# LedLampDriver.net
KiCad netlist of a schematic drawn in Altium Designer
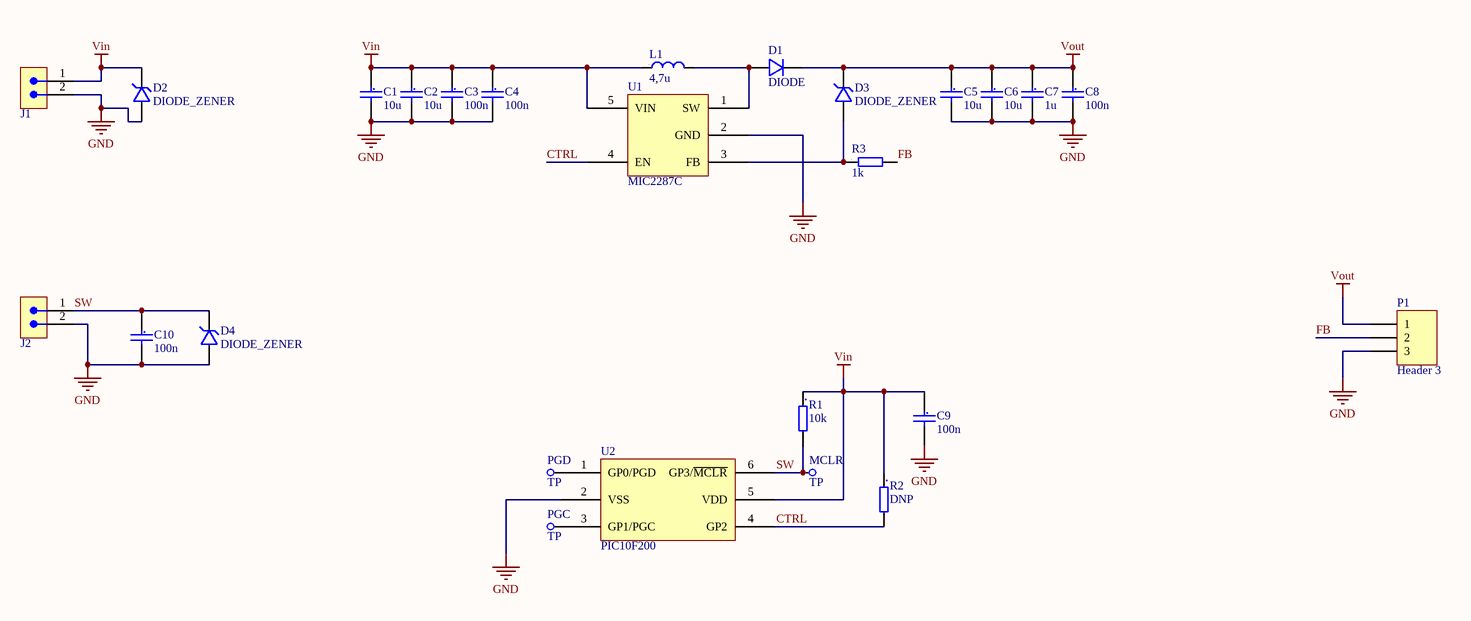
[diagram p0: LedLampDriver.SchDoc]

(export (version "E")
  (design (tool "Eeschema 10.0.6"))
  (components
    (comp (ref "C1") (value "10u") (footprint "C0805_N") (libsource (lib "MyLib") (part "CAP")))
    (comp (ref "C2") (value "10u") (footprint "C0603_N") (libsource (lib "MyLib") (part "CAP")))
    (comp (ref "C3") (value "100n") (footprint "C0805_N") (libsource (lib "MyLib") (part "CAP")))
    (comp (ref "C4") (value "100n") (footprint "C0603_N") (libsource (lib "MyLib") (part "CAP")))
    (comp (ref "C5") (value "10u") (footprint "C0805_N") (libsource (lib "MyLib") (part "CAP")))
    (comp (ref "C6") (value "10u") (footprint "C0805_N") (libsource (lib "MyLib") (part "CAP")))
    (comp (ref "C7") (value "1u") (footprint "C0603_N") (libsource (lib "MyLib") (part "CAP")))
    (comp (ref "C8") (value "100n") (footprint "C0603_N") (libsource (lib "MyLib") (part "CAP")))
    (comp (ref "C9") (value "100n") (footprint "C0603_N") (libsource (lib "MyLib") (part "CAP")))
    (comp (ref "C10") (value "100n") (footprint "C0603_N") (libsource (lib "MyLib") (part "CAP")))
    (comp (ref "D1") (value "DIODE") (footprint "SOD-123") (libsource (lib "MyLib") (part "DIODE")))
    (comp (ref "D2")
      (value "DIODE_ZENER")
      (footprint "SOD-123")
      (libsource (lib "MyLib") (part "DIODE_ZENER"))
    )
    (comp (ref "D3")
      (value "DIODE_ZENER")
      (footprint "SOD-123")
      (libsource (lib "MyLib") (part "DIODE_ZENER"))
    )
    (comp (ref "D4")
      (value "DIODE_ZENER")
      (footprint "SOD-123")
      (libsource (lib "MyLib") (part "DIODE_ZENER"))
    )
    (comp (ref "J1")
      (value "~")
      (footprint "B2B-XH-A")
      (description "Socket")
      (libsource (lib "MyLib") (part "PINHDR_2X1"))
    )
    (comp (ref "J2")
      (value "~")
      (footprint "B2B-XH-A")
      (description "Socket")
      (libsource (lib "MyLib") (part "PINHDR_2X1"))
    )
    (comp (ref "L1")
      (value "4,7u")
      (footprint "IND_2520")
      (description "Inductor")
      (libsource (lib "MyLib") (part "IND"))
    )
    (comp (ref "MCLR") (value "TP") (footprint "TP_1MM") (libsource (lib "MyLib") (part "TP")))
    (comp (ref "P1")
      (value "Header 3")
      (footprint "HDR1X3")
      (description "Header, 3-Pin")
      (fields (field (name "PUBLISHER") "Altium Limited"))
      (libsource (lib "Miscellaneous Connectors") (part "Header 3"))
    )
    (comp (ref "PGC") (value "TP") (footprint "TP_1MM") (libsource (lib "MyLib") (part "TP")))
    (comp (ref "PGD") (value "TP") (footprint "TP_1MM") (libsource (lib "MyLib") (part "TP")))
    (comp (ref "R1") (value "10k") (footprint "R0603_N") (libsource (lib "MyLib") (part "RES")))
    (comp (ref "R2") (value "DNP") (footprint "R0402_N") (libsource (lib "MyLib") (part "RES")))
    (comp (ref "R3") (value "1k") (footprint "R0402_N") (libsource (lib "MyLib") (part "RES")))
    (comp (ref "U1")
      (value "MIC2287C")
      (footprint "SOT23-5")
      (description "1.2MHz PWM White LED Driver with OVP in\r\n2mm × 2mm MLF™ and Thin SOT-23")
      (libsource (lib "MyLib") (part "MIC2287C"))
    )
    (comp (ref "U2")
      (value "PIC10F200")
      (footprint "SOT23-6")
      (description "6-Pin, 8-Bit Flash MCU")
      (libsource (lib "MyLib") (part "PIC10F200"))
    )
  )
  (nets
    (net (code "1") (name "/CTRL") (class "Default")
      (node (ref "R2") (pin "2") (pinfunction "2_2") (pintype "passive"))
      (node (ref "U1") (pin "4") (pinfunction "EN_4") (pintype "passive"))
      (node (ref "U2") (pin "4") (pinfunction "GP2_4") (pintype "passive"))
    )
    (net (code "2") (name "/FB") (class "Default")
      (node (ref "P1") (pin "2") (pinfunction "2_2") (pintype "passive"))
      (node (ref "R3") (pin "2") (pinfunction "2_2") (pintype "passive"))
    )
    (net (code "3") (name "/SW") (class "Default")
      (node (ref "C10") (pin "1") (pinfunction "1_1") (pintype "passive"))
      (node (ref "D4") (pin "C") (pinfunction "C_C") (pintype "passive"))
      (node (ref "J2") (pin "1") (pinfunction "1_1") (pintype "passive"))
      (node (ref "MCLR") (pin "1") (pinfunction "1_1") (pintype "passive"))
      (node (ref "R1") (pin "2") (pinfunction "2_2") (pintype "passive"))
      (node (ref "U2") (pin "6") (pinfunction "GP3/~{MCLR}_6") (pintype "passive"))
    )
    (net (code "4") (name "GND") (class "Default")
      (node (ref "C1") (pin "2") (pinfunction "2_2") (pintype "passive"))
      (node (ref "C10") (pin "2") (pinfunction "2_2") (pintype "passive"))
      (node (ref "C2") (pin "2") (pinfunction "2_2") (pintype "passive"))
      (node (ref "C3") (pin "2") (pinfunction "2_2") (pintype "passive"))
      (node (ref "C4") (pin "2") (pinfunction "2_2") (pintype "passive"))
      (node (ref "C5") (pin "2") (pinfunction "2_2") (pintype "passive"))
      (node (ref "C6") (pin "2") (pinfunction "2_2") (pintype "passive"))
      (node (ref "C7") (pin "2") (pinfunction "2_2") (pintype "passive"))
      (node (ref "C8") (pin "2") (pinfunction "2_2") (pintype "passive"))
      (node (ref "C9") (pin "2") (pinfunction "2_2") (pintype "passive"))
      (node (ref "D2") (pin "A") (pinfunction "A_A") (pintype "passive"))
      (node (ref "D4") (pin "A") (pinfunction "A_A") (pintype "passive"))
      (node (ref "J1") (pin "2") (pinfunction "2_2") (pintype "passive"))
      (node (ref "J2") (pin "2") (pinfunction "2_2") (pintype "passive"))
      (node (ref "P1") (pin "3") (pinfunction "3_3") (pintype "passive"))
      (node (ref "U1") (pin "2") (pinfunction "GND_2") (pintype "passive"))
      (node (ref "U2") (pin "2") (pinfunction "VSS_2") (pintype "passive"))
    )
    (net (code "5") (name "Net-(U1-FB)") (class "Default")
      (node (ref "D3") (pin "A") (pinfunction "A_A") (pintype "passive"))
      (node (ref "R3") (pin "1") (pinfunction "1_1") (pintype "passive"))
      (node (ref "U1") (pin "3") (pinfunction "FB_3") (pintype "passive"))
    )
    (net (code "6") (name "Net-(U1-SW)") (class "Default")
      (node (ref "D1") (pin "A") (pinfunction "A_A") (pintype "passive"))
      (node (ref "L1") (pin "2") (pinfunction "2_2") (pintype "passive"))
      (node (ref "U1") (pin "1") (pinfunction "SW_1") (pintype "passive"))
    )
    (net (code "7") (name "Net-(U2-GP0{slash}PGD)") (class "Default")
      (node (ref "PGD") (pin "1") (pinfunction "1_1") (pintype "passive"))
      (node (ref "U2") (pin "1") (pinfunction "GP0/PGD_1") (pintype "passive"))
    )
    (net (code "8") (name "Net-(U2-GP1{slash}PGC)") (class "Default")
      (node (ref "PGC") (pin "1") (pinfunction "1_1") (pintype "passive"))
      (node (ref "U2") (pin "3") (pinfunction "GP1/PGC_3") (pintype "passive"))
    )
    (net (code "9") (name "Vin") (class "Default")
      (node (ref "C1") (pin "1") (pinfunction "1_1") (pintype "passive"))
      (node (ref "C2") (pin "1") (pinfunction "1_1") (pintype "passive"))
      (node (ref "C3") (pin "1") (pinfunction "1_1") (pintype "passive"))
      (node (ref "C4") (pin "1") (pinfunction "1_1") (pintype "passive"))
      (node (ref "C9") (pin "1") (pinfunction "1_1") (pintype "passive"))
      (node (ref "D2") (pin "C") (pinfunction "C_C") (pintype "passive"))
      (node (ref "J1") (pin "1") (pinfunction "1_1") (pintype "passive"))
      (node (ref "L1") (pin "1") (pinfunction "1_1") (pintype "passive"))
      (node (ref "R1") (pin "1") (pinfunction "1_1") (pintype "passive"))
      (node (ref "R2") (pin "1") (pinfunction "1_1") (pintype "passive"))
      (node (ref "U1") (pin "5") (pinfunction "VIN_5") (pintype "passive"))
      (node (ref "U2") (pin "5") (pinfunction "VDD_5") (pintype "passive"))
    )
    (net (code "10") (name "Vout") (class "Default")
      (node (ref "C5") (pin "1") (pinfunction "1_1") (pintype "passive"))
      (node (ref "C6") (pin "1") (pinfunction "1_1") (pintype "passive"))
      (node (ref "C7") (pin "1") (pinfunction "1_1") (pintype "passive"))
      (node (ref "C8") (pin "1") (pinfunction "1_1") (pintype "passive"))
      (node (ref "D1") (pin "C") (pinfunction "C_C") (pintype "passive"))
      (node (ref "D3") (pin "C") (pinfunction "C_C") (pintype "passive"))
      (node (ref "P1") (pin "1") (pinfunction "1_1") (pintype "passive"))
    )
  )
)
